# GaN_Half_Bridge3.net
KiCad netlist of a schematic drawn in Altium Designer
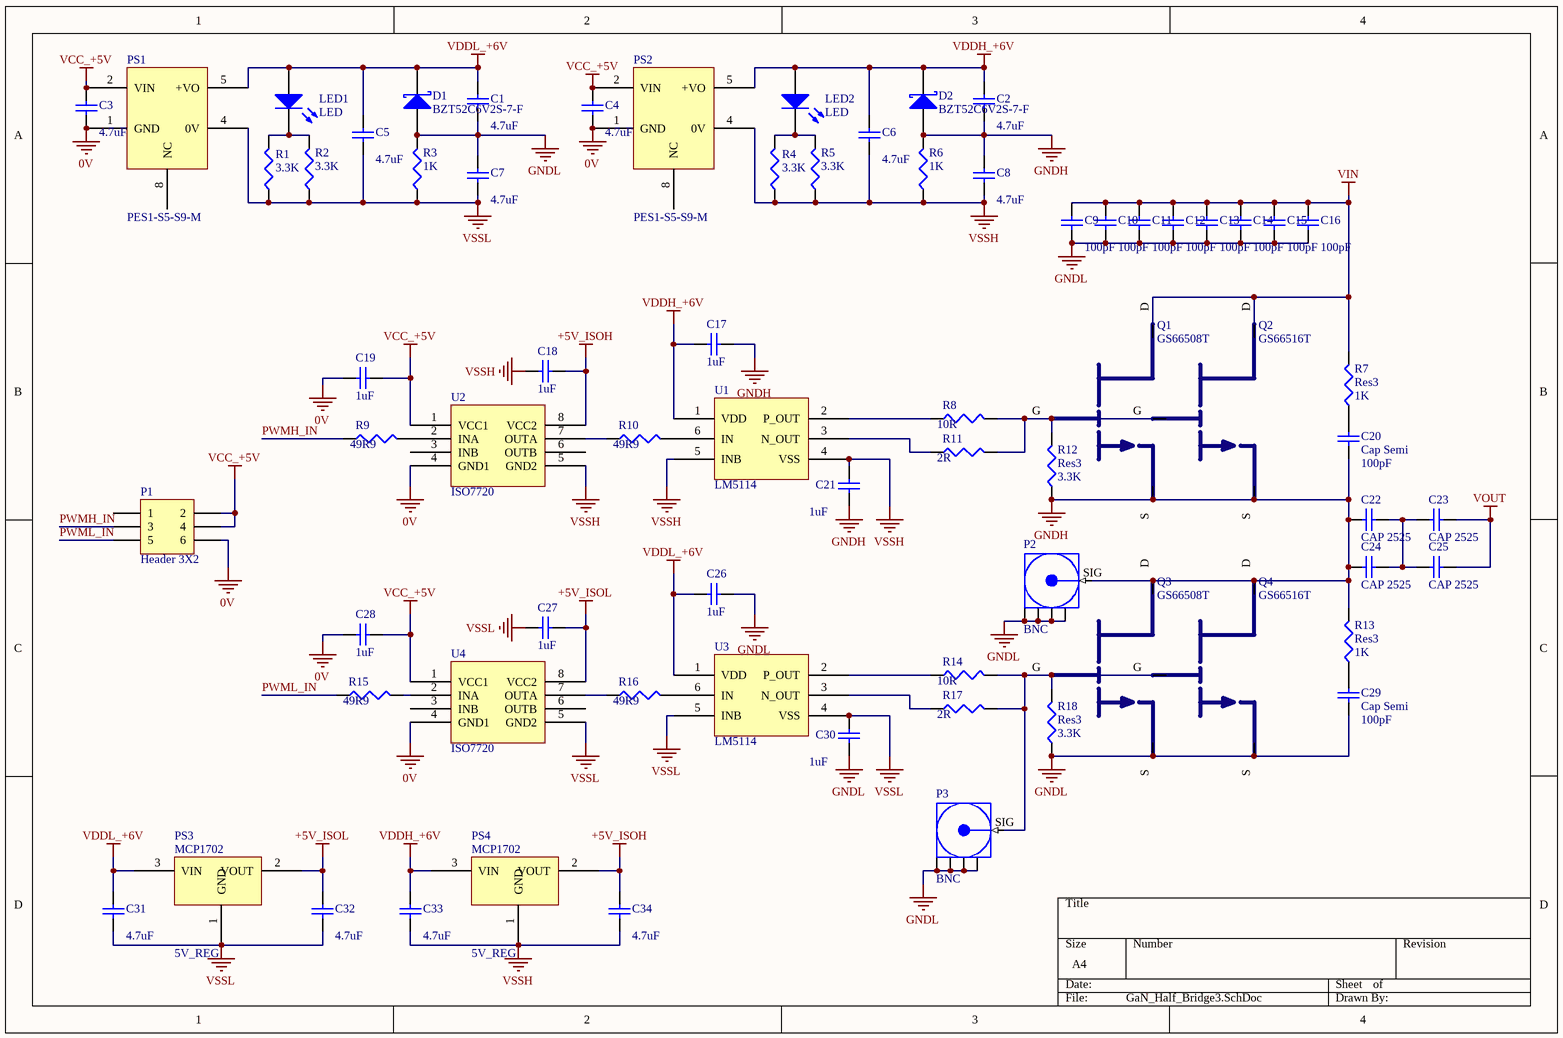
[diagram p0: GaN_Half_Bridge3.SchDoc]

(export (version "E")
  (design (tool "Eeschema 10.0.6"))
  (components
    (comp (ref "C1")
      (value "4.7uF")
      (footprint "0805 IPC Low Density")
      (description "Capacitor (Semiconductor SIM Model)")
      (fields (field (name "Comment") "Cap Semi") (field (name "PUBLISHER") "Altium Limited"))
      (libsource (lib "Miscellaneous Devices") (part "Cap Semi"))
    )
    (comp (ref "C2")
      (value "4.7uF")
      (footprint "0805 IPC Low Density")
      (description "Capacitor (Semiconductor SIM Model)")
      (fields (field (name "Comment") "Cap Semi") (field (name "PUBLISHER") "Altium Limited"))
      (libsource (lib "Miscellaneous Devices") (part "Cap Semi"))
    )
    (comp (ref "C3")
      (value "4.7uF")
      (footprint "0805 IPC Low Density")
      (description "Capacitor (Semiconductor SIM Model)")
      (fields (field (name "Comment") "Cap Semi") (field (name "PUBLISHER") "Altium Limited"))
      (libsource (lib "Miscellaneous Devices") (part "Cap Semi"))
    )
    (comp (ref "C4")
      (value "4.7uF")
      (footprint "0805 IPC Low Density")
      (description "Capacitor (Semiconductor SIM Model)")
      (fields (field (name "Comment") "Cap Semi") (field (name "PUBLISHER") "Altium Limited"))
      (libsource (lib "Miscellaneous Devices") (part "Cap Semi"))
    )
    (comp (ref "C5")
      (value "4.7uF")
      (footprint "0805 IPC Low Density")
      (description "Capacitor (Semiconductor SIM Model)")
      (fields (field (name "Comment") "Cap Semi") (field (name "PUBLISHER") "Altium Limited"))
      (libsource (lib "Miscellaneous Devices") (part "Cap Semi"))
    )
    (comp (ref "C6")
      (value "4.7uF")
      (footprint "0805 IPC Low Density")
      (description "Capacitor (Semiconductor SIM Model)")
      (fields (field (name "Comment") "Cap Semi") (field (name "PUBLISHER") "Altium Limited"))
      (libsource (lib "Miscellaneous Devices") (part "Cap Semi"))
    )
    (comp (ref "C7")
      (value "4.7uF")
      (footprint "0805 IPC Low Density")
      (description "Capacitor (Semiconductor SIM Model)")
      (fields (field (name "Comment") "Cap Semi") (field (name "PUBLISHER") "Altium Limited"))
      (libsource (lib "Miscellaneous Devices") (part "Cap Semi"))
    )
    (comp (ref "C8")
      (value "4.7uF")
      (footprint "0805 IPC Low Density")
      (description "Capacitor (Semiconductor SIM Model)")
      (fields (field (name "Comment") "Cap Semi") (field (name "PUBLISHER") "Altium Limited"))
      (libsource (lib "Miscellaneous Devices") (part "Cap Semi"))
    )
    (comp (ref "C9")
      (value "100pF")
      (footprint "1812 IPC Low Density")
      (description "Capacitor (Semiconductor SIM Model)")
      (fields (field (name "Comment") "Cap Semi") (field (name "PUBLISHER") "Altium Limited"))
      (libsource (lib "Miscellaneous Devices") (part "Cap Semi"))
    )
    (comp (ref "C10")
      (value "100pF")
      (footprint "1812 IPC Low Density")
      (description "Capacitor (Semiconductor SIM Model)")
      (fields (field (name "Comment") "Cap Semi") (field (name "PUBLISHER") "Altium Limited"))
      (libsource (lib "Miscellaneous Devices") (part "Cap Semi"))
    )
    (comp (ref "C11")
      (value "100pF")
      (footprint "1812 IPC Low Density")
      (description "Capacitor (Semiconductor SIM Model)")
      (fields (field (name "Comment") "Cap Semi") (field (name "PUBLISHER") "Altium Limited"))
      (libsource (lib "Miscellaneous Devices") (part "Cap Semi"))
    )
    (comp (ref "C12")
      (value "100pF")
      (footprint "1812 IPC Low Density")
      (description "Capacitor (Semiconductor SIM Model)")
      (fields (field (name "Comment") "Cap Semi") (field (name "PUBLISHER") "Altium Limited"))
      (libsource (lib "Miscellaneous Devices") (part "Cap Semi"))
    )
    (comp (ref "C13")
      (value "100pF")
      (footprint "1812 IPC Low Density")
      (description "Capacitor (Semiconductor SIM Model)")
      (fields (field (name "Comment") "Cap Semi") (field (name "PUBLISHER") "Altium Limited"))
      (libsource (lib "Miscellaneous Devices") (part "Cap Semi"))
    )
    (comp (ref "C14")
      (value "100pF")
      (footprint "1812 IPC Low Density")
      (description "Capacitor (Semiconductor SIM Model)")
      (fields (field (name "Comment") "Cap Semi") (field (name "PUBLISHER") "Altium Limited"))
      (libsource (lib "Miscellaneous Devices") (part "Cap Semi"))
    )
    (comp (ref "C15")
      (value "100pF")
      (footprint "1812 IPC Low Density")
      (description "Capacitor (Semiconductor SIM Model)")
      (fields (field (name "Comment") "Cap Semi") (field (name "PUBLISHER") "Altium Limited"))
      (libsource (lib "Miscellaneous Devices") (part "Cap Semi"))
    )
    (comp (ref "C16")
      (value "100pF")
      (footprint "1812 IPC Low Density")
      (description "Capacitor (Semiconductor SIM Model)")
      (fields (field (name "Comment") "Cap Semi") (field (name "PUBLISHER") "Altium Limited"))
      (libsource (lib "Miscellaneous Devices") (part "Cap Semi"))
    )
    (comp (ref "C17")
      (value "1uF")
      (footprint "0603 IPC Low Density")
      (description "Capacitor (Semiconductor SIM Model)")
      (fields (field (name "Comment") "Cap Semi") (field (name "PUBLISHER") "Altium Limited"))
      (libsource (lib "Miscellaneous Devices") (part "Cap Semi"))
    )
    (comp (ref "C18")
      (value "1uF")
      (footprint "0603 IPC Low Density")
      (description "Capacitor (Semiconductor SIM Model)")
      (fields (field (name "Comment") "Cap Semi") (field (name "PUBLISHER") "Altium Limited"))
      (libsource (lib "Miscellaneous Devices") (part "Cap Semi"))
    )
    (comp (ref "C19")
      (value "1uF")
      (footprint "0603 IPC Low Density")
      (description "Capacitor (Semiconductor SIM Model)")
      (fields (field (name "Comment") "Cap Semi") (field (name "PUBLISHER") "Altium Limited"))
      (libsource (lib "Miscellaneous Devices") (part "Cap Semi"))
    )
    (comp (ref "C20")
      (value "Cap Semi")
      (footprint "1206 IPC Low Density")
      (description "Capacitor (Semiconductor SIM Model)")
      (fields (field (name "ALTIUM_VALUE") "100pF") (field (name "PUBLISHER") "Altium Limited"))
      (libsource (lib "Miscellaneous Devices") (part "Cap Semi"))
    )
    (comp (ref "C21")
      (value "1uF")
      (footprint "0603 IPC Low Density")
      (description "Capacitor (Semiconductor SIM Model)")
      (fields (field (name "Comment") "Cap Semi") (field (name "PUBLISHER") "Altium Limited"))
      (libsource (lib "Miscellaneous Devices") (part "Cap Semi"))
    )
    (comp (ref "C22")
      (value "CAP 2525")
      (footprint "CAP 2525")
      (libsource (lib "GaN_Schlib") (part "CAP 2525"))
    )
    (comp (ref "C23")
      (value "CAP 2525")
      (footprint "CAP 2525")
      (libsource (lib "GaN_Schlib") (part "CAP 2525"))
    )
    (comp (ref "C24")
      (value "CAP 2525")
      (footprint "CAP 2525")
      (libsource (lib "GaN_Schlib") (part "CAP 2525"))
    )
    (comp (ref "C25")
      (value "CAP 2525")
      (footprint "CAP 2525")
      (libsource (lib "GaN_Schlib") (part "CAP 2525"))
    )
    (comp (ref "C26")
      (value "1uF")
      (footprint "0603 IPC Low Density")
      (description "Capacitor (Semiconductor SIM Model)")
      (fields (field (name "Comment") "Cap Semi") (field (name "PUBLISHER") "Altium Limited"))
      (libsource (lib "Miscellaneous Devices") (part "Cap Semi"))
    )
    (comp (ref "C27")
      (value "1uF")
      (footprint "0603 IPC Low Density")
      (description "Capacitor (Semiconductor SIM Model)")
      (fields (field (name "Comment") "Cap Semi") (field (name "PUBLISHER") "Altium Limited"))
      (libsource (lib "Miscellaneous Devices") (part "Cap Semi"))
    )
    (comp (ref "C28")
      (value "1uF")
      (footprint "0603 IPC Low Density")
      (description "Capacitor (Semiconductor SIM Model)")
      (fields (field (name "Comment") "Cap Semi") (field (name "PUBLISHER") "Altium Limited"))
      (libsource (lib "Miscellaneous Devices") (part "Cap Semi"))
    )
    (comp (ref "C29")
      (value "Cap Semi")
      (footprint "1206 IPC Low Density")
      (description "Capacitor (Semiconductor SIM Model)")
      (fields (field (name "ALTIUM_VALUE") "100pF") (field (name "PUBLISHER") "Altium Limited"))
      (libsource (lib "Miscellaneous Devices") (part "Cap Semi"))
    )
    (comp (ref "C30")
      (value "1uF")
      (footprint "0603 IPC Low Density")
      (description "Capacitor (Semiconductor SIM Model)")
      (fields (field (name "Comment") "Cap Semi") (field (name "PUBLISHER") "Altium Limited"))
      (libsource (lib "Miscellaneous Devices") (part "Cap Semi"))
    )
    (comp (ref "C31")
      (value "4.7uF")
      (footprint "0805 IPC Low Density")
      (description "Capacitor (Semiconductor SIM Model)")
      (fields (field (name "Comment") "Cap Semi") (field (name "PUBLISHER") "Altium Limited"))
      (libsource (lib "Miscellaneous Devices") (part "Cap Semi"))
    )
    (comp (ref "C32")
      (value "4.7uF")
      (footprint "0805 IPC Low Density")
      (description "Capacitor (Semiconductor SIM Model)")
      (fields (field (name "Comment") "Cap Semi") (field (name "PUBLISHER") "Altium Limited"))
      (libsource (lib "Miscellaneous Devices") (part "Cap Semi"))
    )
    (comp (ref "C33")
      (value "4.7uF")
      (footprint "0805 IPC Low Density")
      (description "Capacitor (Semiconductor SIM Model)")
      (fields (field (name "Comment") "Cap Semi") (field (name "PUBLISHER") "Altium Limited"))
      (libsource (lib "Miscellaneous Devices") (part "Cap Semi"))
    )
    (comp (ref "C34")
      (value "4.7uF")
      (footprint "0805 IPC Low Density")
      (description "Capacitor (Semiconductor SIM Model)")
      (fields (field (name "Comment") "Cap Semi") (field (name "PUBLISHER") "Altium Limited"))
      (libsource (lib "Miscellaneous Devices") (part "Cap Semi"))
    )
    (comp (ref "D1")
      (value "BZT52C6V2S-7-F")
      (footprint "SOD-323")
      (description "Zener Diodes 6.2V 200mW")
      (libsource (lib "GaN_Schlib") (part "BZT52C6V2S-7-F"))
    )
    (comp (ref "D2")
      (value "BZT52C6V2S-7-F")
      (footprint "SOD-323")
      (description "Zener Diodes 6.2V 200mW")
      (libsource (lib "GaN_Schlib") (part "BZT52C6V2S-7-F"))
    )
    (comp (ref "LED1")
      (value "LED")
      (footprint "LED 0603")
      (description "SML-D12U1WT86")
      (libsource (lib "GaN_Schlib") (part "LED"))
    )
    (comp (ref "LED2")
      (value "LED")
      (footprint "LED 0603")
      (description "SML-D12U1WT86")
      (libsource (lib "GaN_Schlib") (part "LED"))
    )
    (comp (ref "P1")
      (value "Header 3X2")
      (footprint "HDR2X3")
      (description "Header, 3-Pin, Dual row")
      (fields (field (name "PUBLISHER") "Altium Limited"))
      (libsource (lib "Miscellaneous Connectors") (part "Header 3X2"))
    )
    (comp (ref "P2")
      (value "BNC")
      (footprint "BNC")
      (description "Straight 50Ω Through Hole BNC Connector")
      (fields (field (name "PUBLISHER") "Altium Limited"))
      (libsource (lib "GaN_Schlib") (part "BNC"))
    )
    (comp (ref "P3")
      (value "BNC")
      (footprint "BNC")
      (description "Straight 50Ω Through Hole BNC Connector")
      (fields (field (name "PUBLISHER") "Altium Limited"))
      (libsource (lib "GaN_Schlib") (part "BNC"))
    )
    (comp (ref "PS1")
      (value "PES1-S5-S9-M")
      (footprint "PES1-S5-S9-M")
      (libsource (lib "GaN_Schlib") (part "PES1-S5-S9-M"))
    )
    (comp (ref "PS2")
      (value "PES1-S5-S9-M")
      (footprint "PES1-S5-S9-M")
      (libsource (lib "GaN_Schlib") (part "PES1-S5-S9-M"))
    )
    (comp (ref "PS3") (value "5V_REG") (footprint "SOT23-3") (libsource (lib "GaN_Schlib") (part "5V_REG")))
    (comp (ref "PS4") (value "5V_REG") (footprint "SOT23-3") (libsource (lib "GaN_Schlib") (part "5V_REG")))
    (comp (ref "Q1")
      (value "GS66508T")
      (footprint "GS66508T")
      (description "650 V E-HEMT - Top Side Cooled")
      (libsource (lib "GaN_Schlib") (part "GS66508P"))
    )
    (comp (ref "Q2")
      (value "GS66516T")
      (footprint "GS66516T")
      (description "Top-side cooled 650 V E-mode GaN transistor")
      (libsource (lib "GaN_Schlib") (part "GS66516T"))
    )
    (comp (ref "Q3")
      (value "GS66508T")
      (footprint "GS66508T")
      (description "650 V E-HEMT - Top Side Cooled")
      (libsource (lib "GaN_Schlib") (part "GS66508P"))
    )
    (comp (ref "Q4")
      (value "GS66516T")
      (footprint "GS66516T")
      (description "Top-side cooled 650 V E-mode GaN transistor")
      (libsource (lib "GaN_Schlib") (part "GS66516T"))
    )
    (comp (ref "R1")
      (value "3.3K")
      (footprint "RESISTOR 0603")
      (description "Resistor")
      (fields (field (name "Comment") "Res3") (field (name "PUBLISHER") "Altium Limited"))
      (libsource (lib "Miscellaneous Devices") (part "Res3"))
    )
    (comp (ref "R2")
      (value "3.3K")
      (footprint "RESISTOR 0603")
      (description "Resistor")
      (fields (field (name "Comment") "Res3") (field (name "PUBLISHER") "Altium Limited"))
      (libsource (lib "Miscellaneous Devices") (part "Res3"))
    )
    (comp (ref "R3")
      (value "1K")
      (footprint "RESISTOR 0603")
      (description "Resistor")
      (fields (field (name "Comment") "Res3") (field (name "PUBLISHER") "Altium Limited"))
      (libsource (lib "Miscellaneous Devices") (part "Res3"))
    )
    (comp (ref "R4")
      (value "3.3K")
      (footprint "RESISTOR 0603")
      (description "Resistor")
      (fields (field (name "Comment") "Res3") (field (name "PUBLISHER") "Altium Limited"))
      (libsource (lib "Miscellaneous Devices") (part "Res3"))
    )
    (comp (ref "R5")
      (value "3.3K")
      (footprint "RESISTOR 0603")
      (description "Resistor")
      (fields (field (name "Comment") "Res3") (field (name "PUBLISHER") "Altium Limited"))
      (libsource (lib "Miscellaneous Devices") (part "Res3"))
    )
    (comp (ref "R6")
      (value "1K")
      (footprint "RESISTOR 0603")
      (description "Resistor")
      (fields (field (name "Comment") "Res3") (field (name "PUBLISHER") "Altium Limited"))
      (libsource (lib "Miscellaneous Devices") (part "Res3"))
    )
    (comp (ref "R7")
      (value "Res3")
      (footprint "RESISTOR 1206")
      (description "Resistor")
      (fields (field (name "ALTIUM_VALUE") "1K") (field (name "PUBLISHER") "Altium Limited"))
      (libsource (lib "Miscellaneous Devices") (part "Res3"))
    )
    (comp (ref "R8")
      (value "10R")
      (footprint "RESISTOR 0603")
      (description "Resistor")
      (fields (field (name "Comment") "Res3") (field (name "PUBLISHER") "Altium Limited"))
      (libsource (lib "Miscellaneous Devices") (part "Res3"))
    )
    (comp (ref "R9")
      (value "49R9")
      (footprint "RESISTOR 0603")
      (description "Resistor")
      (fields (field (name "Comment") "Res3") (field (name "PUBLISHER") "Altium Limited"))
      (libsource (lib "Miscellaneous Devices") (part "Res3"))
    )
    (comp (ref "R10")
      (value "49R9")
      (footprint "RESISTOR 0603")
      (description "Resistor")
      (fields (field (name "Comment") "Res3") (field (name "PUBLISHER") "Altium Limited"))
      (libsource (lib "Miscellaneous Devices") (part "Res3"))
    )
    (comp (ref "R11")
      (value "2R")
      (footprint "RESISTOR 0603")
      (description "Resistor")
      (fields (field (name "Comment") "Res3") (field (name "PUBLISHER") "Altium Limited"))
      (libsource (lib "Miscellaneous Devices") (part "Res3"))
    )
    (comp (ref "R12")
      (value "Res3")
      (footprint "RESISTOR 0603")
      (description "Resistor")
      (fields (field (name "ALTIUM_VALUE") "3.3K") (field (name "PUBLISHER") "Altium Limited"))
      (libsource (lib "Miscellaneous Devices") (part "Res3"))
    )
    (comp (ref "R13")
      (value "Res3")
      (footprint "RESISTOR 1206")
      (description "Resistor")
      (fields (field (name "ALTIUM_VALUE") "1K") (field (name "PUBLISHER") "Altium Limited"))
      (libsource (lib "Miscellaneous Devices") (part "Res3"))
    )
    (comp (ref "R14")
      (value "10R")
      (footprint "RESISTOR 0603")
      (description "Resistor")
      (fields (field (name "Comment") "Res3") (field (name "PUBLISHER") "Altium Limited"))
      (libsource (lib "Miscellaneous Devices") (part "Res3"))
    )
    (comp (ref "R15")
      (value "49R9")
      (footprint "RESISTOR 0603")
      (description "Resistor")
      (fields (field (name "Comment") "Res3") (field (name "PUBLISHER") "Altium Limited"))
      (libsource (lib "Miscellaneous Devices") (part "Res3"))
    )
    (comp (ref "R16")
      (value "49R9")
      (footprint "RESISTOR 0603")
      (description "Resistor")
      (fields (field (name "Comment") "Res3") (field (name "PUBLISHER") "Altium Limited"))
      (libsource (lib "Miscellaneous Devices") (part "Res3"))
    )
    (comp (ref "R17")
      (value "2R")
      (footprint "RESISTOR 0603")
      (description "Resistor")
      (fields (field (name "Comment") "Res3") (field (name "PUBLISHER") "Altium Limited"))
      (libsource (lib "Miscellaneous Devices") (part "Res3"))
    )
    (comp (ref "R18")
      (value "Res3")
      (footprint "RESISTOR 0603")
      (description "Resistor")
      (fields (field (name "ALTIUM_VALUE") "3.3K") (field (name "PUBLISHER") "Altium Limited"))
      (libsource (lib "Miscellaneous Devices") (part "Res3"))
    )
    (comp (ref "U1") (value "LM5114") (footprint "WSON") (libsource (lib "GaN_Schlib") (part "LM5114")))
    (comp (ref "U2") (value "ISO7720") (footprint "SOIC8_N") (libsource (lib "GaN_Schlib") (part "ISO7720")))
    (comp (ref "U3") (value "LM5114") (footprint "WSON") (libsource (lib "GaN_Schlib") (part "LM5114")))
    (comp (ref "U4") (value "ISO7720") (footprint "SOIC8_N") (libsource (lib "GaN_Schlib") (part "ISO7720")))
  )
  (nets
    (net (code "1") (name "+5V_ISOH") (class "Default")
      (node (ref "C18") (pin "1") (pinfunction "1_1") (pintype "passive"))
      (node (ref "C34") (pin "2") (pinfunction "2_2") (pintype "passive"))
      (node (ref "PS4") (pin "2") (pinfunction "VOUT_2") (pintype "passive"))
      (node (ref "U2") (pin "8") (pinfunction "VCC2_8") (pintype "passive"))
    )
    (net (code "2") (name "+5V_ISOL") (class "Default")
      (node (ref "C27") (pin "1") (pinfunction "1_1") (pintype "passive"))
      (node (ref "C32") (pin "2") (pinfunction "2_2") (pintype "passive"))
      (node (ref "PS3") (pin "2") (pinfunction "VOUT_2") (pintype "passive"))
      (node (ref "U4") (pin "8") (pinfunction "VCC2_8") (pintype "passive"))
    )
    (net (code "3") (name "/PWMH_IN") (class "Default")
      (node (ref "P1") (pin "3") (pinfunction "3_3") (pintype "passive"))
      (node (ref "R9") (pin "1") (pinfunction "1_1") (pintype "passive"))
    )
    (net (code "4") (name "/PWML_IN") (class "Default")
      (node (ref "P1") (pin "5") (pinfunction "5_5") (pintype "passive"))
      (node (ref "R15") (pin "1") (pinfunction "1_1") (pintype "passive"))
    )
    (net (code "5") (name "0V") (class "Default")
      (node (ref "C19") (pin "2") (pinfunction "2_2") (pintype "passive"))
      (node (ref "C28") (pin "2") (pinfunction "2_2") (pintype "passive"))
      (node (ref "C3") (pin "1") (pinfunction "1_1") (pintype "passive"))
      (node (ref "C4") (pin "1") (pinfunction "1_1") (pintype "passive"))
      (node (ref "P1") (pin "6") (pinfunction "6_6") (pintype "passive"))
      (node (ref "PS1") (pin "1") (pinfunction "GND_1") (pintype "passive"))
      (node (ref "PS2") (pin "1") (pinfunction "GND_1") (pintype "passive"))
      (node (ref "U2") (pin "4") (pinfunction "GND1_4") (pintype "passive"))
      (node (ref "U4") (pin "4") (pinfunction "GND1_4") (pintype "passive"))
    )
    (net (code "6") (name "GNDH") (class "Default")
      (node (ref "C17") (pin "1") (pinfunction "1_1") (pintype "passive"))
      (node (ref "C2") (pin "1") (pinfunction "1_1") (pintype "passive"))
      (node (ref "C20") (pin "1") (pinfunction "1_1") (pintype "passive"))
      (node (ref "C21") (pin "1") (pinfunction "1_1") (pintype "passive"))
      (node (ref "C22") (pin "1") (pinfunction "1_1") (pintype "passive"))
      (node (ref "C24") (pin "1") (pinfunction "1_1") (pintype "passive"))
      (node (ref "C8") (pin "2") (pinfunction "2_2") (pintype "passive"))
      (node (ref "D2") (pin "1") (pinfunction "A_1") (pintype "passive"))
      (node (ref "P2") (pin "SIG") (pinfunction "Signal_SIG") (pintype "input"))
      (node (ref "Q1") (pin "S") (pinfunction "S_S") (pintype "passive"))
      (node (ref "Q2") (pin "S") (pinfunction "S_S") (pintype "passive"))
      (node (ref "Q3") (pin "D") (pinfunction "D_D") (pintype "passive"))
      (node (ref "Q4") (pin "D") (pinfunction "D_D") (pintype "passive"))
      (node (ref "R12") (pin "1") (pinfunction "1_1") (pintype "passive"))
      (node (ref "R13") (pin "2") (pinfunction "2_2") (pintype "passive"))
      (node (ref "R6") (pin "2") (pinfunction "2_2") (pintype "passive"))
    )
    (net (code "7") (name "GNDL") (class "Default")
      (node (ref "C1") (pin "1") (pinfunction "1_1") (pintype "passive"))
      (node (ref "C10") (pin "1") (pinfunction "1_1") (pintype "passive"))
      (node (ref "C11") (pin "1") (pinfunction "1_1") (pintype "passive"))
      (node (ref "C12") (pin "1") (pinfunction "1_1") (pintype "passive"))
      (node (ref "C13") (pin "1") (pinfunction "1_1") (pintype "passive"))
      (node (ref "C14") (pin "1") (pinfunction "1_1") (pintype "passive"))
      (node (ref "C15") (pin "1") (pinfunction "1_1") (pintype "passive"))
      (node (ref "C16") (pin "1") (pinfunction "1_1") (pintype "passive"))
      (node (ref "C26") (pin "1") (pinfunction "1_1") (pintype "passive"))
      (node (ref "C29") (pin "1") (pinfunction "1_1") (pintype "passive"))
      (node (ref "C30") (pin "1") (pinfunction "1_1") (pintype "passive"))
      (node (ref "C7") (pin "2") (pinfunction "2_2") (pintype "passive"))
      (node (ref "C9") (pin "1") (pinfunction "1_1") (pintype "passive"))
      (node (ref "D1") (pin "1") (pinfunction "A_1") (pintype "passive"))
      (node (ref "P2") (pin "GND") (pinfunction "GND_GND") (pintype "power_in"))
      (node (ref "P3") (pin "GND") (pinfunction "GND_GND") (pintype "power_in"))
      (node (ref "Q3") (pin "S") (pinfunction "S_S") (pintype "passive"))
      (node (ref "Q4") (pin "S") (pinfunction "S_S") (pintype "passive"))
      (node (ref "R18") (pin "1") (pinfunction "1_1") (pintype "passive"))
      (node (ref "R3") (pin "2") (pinfunction "2_2") (pintype "passive"))
    )
    (net (code "8") (name "Net-(C20-Pad2)") (class "Default")
      (node (ref "C20") (pin "2") (pinfunction "2_2") (pintype "passive"))
      (node (ref "R7") (pin "1") (pinfunction "1_1") (pintype "passive"))
    )
    (net (code "9") (name "Net-(C22-Pad2)") (class "Default")
      (node (ref "C22") (pin "2") (pinfunction "2_2") (pintype "passive"))
      (node (ref "C23") (pin "1") (pinfunction "1_1") (pintype "passive"))
      (node (ref "C24") (pin "2") (pinfunction "2_2") (pintype "passive"))
      (node (ref "C25") (pin "1") (pinfunction "1_1") (pintype "passive"))
    )
    (net (code "10") (name "Net-(C29-Pad2)") (class "Default")
      (node (ref "C29") (pin "2") (pinfunction "2_2") (pintype "passive"))
      (node (ref "R13") (pin "1") (pinfunction "1_1") (pintype "passive"))
    )
    (net (code "11") (name "Net-(LED1-K)") (class "Default")
      (node (ref "LED1") (pin "2") (pinfunction "K_2") (pintype "passive"))
      (node (ref "R1") (pin "2") (pinfunction "2_2") (pintype "passive"))
      (node (ref "R2") (pin "2") (pinfunction "2_2") (pintype "passive"))
    )
    (net (code "12") (name "Net-(LED2-K)") (class "Default")
      (node (ref "LED2") (pin "2") (pinfunction "K_2") (pintype "passive"))
      (node (ref "R4") (pin "2") (pinfunction "2_2") (pintype "passive"))
      (node (ref "R5") (pin "2") (pinfunction "2_2") (pintype "passive"))
    )
    (net (code "13") (name "Net-(P3-Signal)") (class "Default")
      (node (ref "P3") (pin "SIG") (pinfunction "Signal_SIG") (pintype "input"))
      (node (ref "Q3") (pin "G") (pinfunction "G_G") (pintype "passive"))
      (node (ref "Q4") (pin "G") (pinfunction "G_G") (pintype "passive"))
      (node (ref "R14") (pin "2") (pinfunction "2_2") (pintype "passive"))
      (node (ref "R17") (pin "2") (pinfunction "2_2") (pintype "passive"))
      (node (ref "R18") (pin "2") (pinfunction "2_2") (pintype "passive"))
    )
    (net (code "14") (name "Net-(Q1-PadG)") (class "Default")
      (node (ref "Q1") (pin "G") (pinfunction "G_G") (pintype "passive"))
      (node (ref "Q2") (pin "G") (pinfunction "G_G") (pintype "passive"))
      (node (ref "R11") (pin "2") (pinfunction "2_2") (pintype "passive"))
      (node (ref "R12") (pin "2") (pinfunction "2_2") (pintype "passive"))
      (node (ref "R8") (pin "2") (pinfunction "2_2") (pintype "passive"))
    )
    (net (code "15") (name "Net-(U1-IN)") (class "Default")
      (node (ref "R10") (pin "2") (pinfunction "2_2") (pintype "passive"))
      (node (ref "U1") (pin "6") (pinfunction "IN_6") (pintype "passive"))
    )
    (net (code "16") (name "Net-(U1-N_OUT)") (class "Default")
      (node (ref "R11") (pin "1") (pinfunction "1_1") (pintype "passive"))
      (node (ref "U1") (pin "3") (pinfunction "N_OUT_3") (pintype "passive"))
    )
    (net (code "17") (name "Net-(U1-P_OUT)") (class "Default")
      (node (ref "R8") (pin "1") (pinfunction "1_1") (pintype "passive"))
      (node (ref "U1") (pin "2") (pinfunction "P_OUT_2") (pintype "passive"))
    )
    (net (code "18") (name "Net-(U2-INA)") (class "Default")
      (node (ref "R9") (pin "2") (pinfunction "2_2") (pintype "passive"))
      (node (ref "U2") (pin "2") (pinfunction "INA_2") (pintype "passive"))
    )
    (net (code "19") (name "Net-(U2-OUTA)") (class "Default")
      (node (ref "R10") (pin "1") (pinfunction "1_1") (pintype "passive"))
      (node (ref "U2") (pin "7") (pinfunction "OUTA_7") (pintype "passive"))
    )
    (net (code "20") (name "Net-(U3-IN)") (class "Default")
      (node (ref "R16") (pin "2") (pinfunction "2_2") (pintype "passive"))
      (node (ref "U3") (pin "6") (pinfunction "IN_6") (pintype "passive"))
    )
    (net (code "21") (name "Net-(U3-N_OUT)") (class "Default")
      (node (ref "R17") (pin "1") (pinfunction "1_1") (pintype "passive"))
      (node (ref "U3") (pin "3") (pinfunction "N_OUT_3") (pintype "passive"))
    )
    (net (code "22") (name "Net-(U3-P_OUT)") (class "Default")
      (node (ref "R14") (pin "1") (pinfunction "1_1") (pintype "passive"))
      (node (ref "U3") (pin "2") (pinfunction "P_OUT_2") (pintype "passive"))
    )
    (net (code "23") (name "Net-(U4-INA)") (class "Default")
      (node (ref "R15") (pin "2") (pinfunction "2_2") (pintype "passive"))
      (node (ref "U4") (pin "2") (pinfunction "INA_2") (pintype "passive"))
    )
    (net (code "24") (name "Net-(U4-OUTA)") (class "Default")
      (node (ref "R16") (pin "1") (pinfunction "1_1") (pintype "passive"))
      (node (ref "U4") (pin "7") (pinfunction "OUTA_7") (pintype "passive"))
    )
    (net (code "25") (name "VCC_+5V") (class "Default")
      (node (ref "C19") (pin "1") (pinfunction "1_1") (pintype "passive"))
      (node (ref "C28") (pin "1") (pinfunction "1_1") (pintype "passive"))
      (node (ref "C3") (pin "2") (pinfunction "2_2") (pintype "passive"))
      (node (ref "C4") (pin "2") (pinfunction "2_2") (pintype "passive"))
      (node (ref "P1") (pin "2") (pinfunction "2_2") (pintype "passive"))
      (node (ref "P1") (pin "4") (pinfunction "4_4") (pintype "passive"))
      (node (ref "PS1") (pin "2") (pinfunction "VIN_2") (pintype "passive"))
      (node (ref "PS2") (pin "2") (pinfunction "VIN_2") (pintype "passive"))
      (node (ref "U2") (pin "1") (pinfunction "VCC1_1") (pintype "passive"))
      (node (ref "U4") (pin "1") (pinfunction "VCC1_1") (pintype "passive"))
    )
    (net (code "26") (name "VDDH_+6V") (class "Default")
      (node (ref "C17") (pin "2") (pinfunction "2_2") (pintype "passive"))
      (node (ref "C2") (pin "2") (pinfunction "2_2") (pintype "passive"))
      (node (ref "C33") (pin "2") (pinfunction "2_2") (pintype "passive"))
      (node (ref "C6") (pin "2") (pinfunction "2_2") (pintype "passive"))
      (node (ref "D2") (pin "3") (pinfunction "K_3") (pintype "passive"))
      (node (ref "LED2") (pin "1") (pinfunction "A_1") (pintype "passive"))
      (node (ref "PS2") (pin "5") (pinfunction "+VO_5") (pintype "passive"))
      (node (ref "PS4") (pin "3") (pinfunction "VIN_3") (pintype "passive"))
      (node (ref "U1") (pin "1") (pinfunction "VDD_1") (pintype "passive"))
    )
    (net (code "27") (name "VDDL_+6V") (class "Default")
      (node (ref "C1") (pin "2") (pinfunction "2_2") (pintype "passive"))
      (node (ref "C26") (pin "2") (pinfunction "2_2") (pintype "passive"))
      (node (ref "C31") (pin "2") (pinfunction "2_2") (pintype "passive"))
      (node (ref "C5") (pin "2") (pinfunction "2_2") (pintype "passive"))
      (node (ref "D1") (pin "3") (pinfunction "K_3") (pintype "passive"))
      (node (ref "LED1") (pin "1") (pinfunction "A_1") (pintype "passive"))
      (node (ref "PS1") (pin "5") (pinfunction "+VO_5") (pintype "passive"))
      (node (ref "PS3") (pin "3") (pinfunction "VIN_3") (pintype "passive"))
      (node (ref "U3") (pin "1") (pinfunction "VDD_1") (pintype "passive"))
    )
    (net (code "28") (name "VIN") (class "Default")
      (node (ref "C10") (pin "2") (pinfunction "2_2") (pintype "passive"))
      (node (ref "C11") (pin "2") (pinfunction "2_2") (pintype "passive"))
      (node (ref "C12") (pin "2") (pinfunction "2_2") (pintype "passive"))
      (node (ref "C13") (pin "2") (pinfunction "2_2") (pintype "passive"))
      (node (ref "C14") (pin "2") (pinfunction "2_2") (pintype "passive"))
      (node (ref "C15") (pin "2") (pinfunction "2_2") (pintype "passive"))
      (node (ref "C16") (pin "2") (pinfunction "2_2") (pintype "passive"))
      (node (ref "C9") (pin "2") (pinfunction "2_2") (pintype "passive"))
      (node (ref "Q1") (pin "D") (pinfunction "D_D") (pintype "passive"))
      (node (ref "Q2") (pin "D") (pinfunction "D_D") (pintype "passive"))
      (node (ref "R7") (pin "2") (pinfunction "2_2") (pintype "passive"))
    )
    (net (code "29") (name "VOUT") (class "Default")
      (node (ref "C23") (pin "2") (pinfunction "2_2") (pintype "passive"))
      (node (ref "C25") (pin "2") (pinfunction "2_2") (pintype "passive"))
    )
    (net (code "30") (name "VSSH") (class "Default")
      (node (ref "C18") (pin "2") (pinfunction "2_2") (pintype "passive"))
      (node (ref "C21") (pin "2") (pinfunction "2_2") (pintype "passive"))
      (node (ref "C33") (pin "1") (pinfunction "1_1") (pintype "passive"))
      (node (ref "C34") (pin "1") (pinfunction "1_1") (pintype "passive"))
      (node (ref "C6") (pin "1") (pinfunction "1_1") (pintype "passive"))
      (node (ref "C8") (pin "1") (pinfunction "1_1") (pintype "passive"))
      (node (ref "PS2") (pin "4") (pinfunction "0V_4") (pintype "passive"))
      (node (ref "PS4") (pin "1") (pinfunction "GND_1") (pintype "passive"))
      (node (ref "R4") (pin "1") (pinfunction "1_1") (pintype "passive"))
      (node (ref "R5") (pin "1") (pinfunction "1_1") (pintype "passive"))
      (node (ref "R6") (pin "1") (pinfunction "1_1") (pintype "passive"))
      (node (ref "U1") (pin "4") (pinfunction "VSS_4") (pintype "passive"))
      (node (ref "U1") (pin "5") (pinfunction "INB_5") (pintype "passive"))
      (node (ref "U2") (pin "5") (pinfunction "GND2_5") (pintype "passive"))
    )
    (net (code "31") (name "VSSL") (class "Default")
      (node (ref "C27") (pin "2") (pinfunction "2_2") (pintype "passive"))
      (node (ref "C30") (pin "2") (pinfunction "2_2") (pintype "passive"))
      (node (ref "C31") (pin "1") (pinfunction "1_1") (pintype "passive"))
      (node (ref "C32") (pin "1") (pinfunction "1_1") (pintype "passive"))
      (node (ref "C5") (pin "1") (pinfunction "1_1") (pintype "passive"))
      (node (ref "C7") (pin "1") (pinfunction "1_1") (pintype "passive"))
      (node (ref "PS1") (pin "4") (pinfunction "0V_4") (pintype "passive"))
      (node (ref "PS3") (pin "1") (pinfunction "GND_1") (pintype "passive"))
      (node (ref "R1") (pin "1") (pinfunction "1_1") (pintype "passive"))
      (node (ref "R2") (pin "1") (pinfunction "1_1") (pintype "passive"))
      (node (ref "R3") (pin "1") (pinfunction "1_1") (pintype "passive"))
      (node (ref "U3") (pin "4") (pinfunction "VSS_4") (pintype "passive"))
      (node (ref "U3") (pin "5") (pinfunction "INB_5") (pintype "passive"))
      (node (ref "U4") (pin "5") (pinfunction "GND2_5") (pintype "passive"))
    )
    (net (code "32") (name "unconnected-(P1-Pad1)") (class "Default")
      (node (ref "P1") (pin "1") (pinfunction "1_1") (pintype "passive"))
    )
    (net (code "33") (name "unconnected-(PS1-NC-Pad8)") (class "Default")
      (node (ref "PS1") (pin "8") (pinfunction "NC_8") (pintype "passive"))
    )
    (net (code "34") (name "unconnected-(PS2-NC-Pad8)") (class "Default")
      (node (ref "PS2") (pin "8") (pinfunction "NC_8") (pintype "passive"))
    )
    (net (code "35") (name "unconnected-(U2-INB-Pad3)") (class "Default")
      (node (ref "U2") (pin "3") (pinfunction "INB_3") (pintype "passive"))
    )
    (net (code "36") (name "unconnected-(U2-OUTB-Pad6)") (class "Default")
      (node (ref "U2") (pin "6") (pinfunction "OUTB_6") (pintype "passive"))
    )
    (net (code "37") (name "unconnected-(U4-INB-Pad3)") (class "Default")
      (node (ref "U4") (pin "3") (pinfunction "INB_3") (pintype "passive"))
    )
    (net (code "38") (name "unconnected-(U4-OUTB-Pad6)") (class "Default")
      (node (ref "U4") (pin "6") (pinfunction "OUTB_6") (pintype "passive"))
    )
  )
)
